# Loguino_v1_3.net
KiCad netlist of a schematic drawn in EAGLE
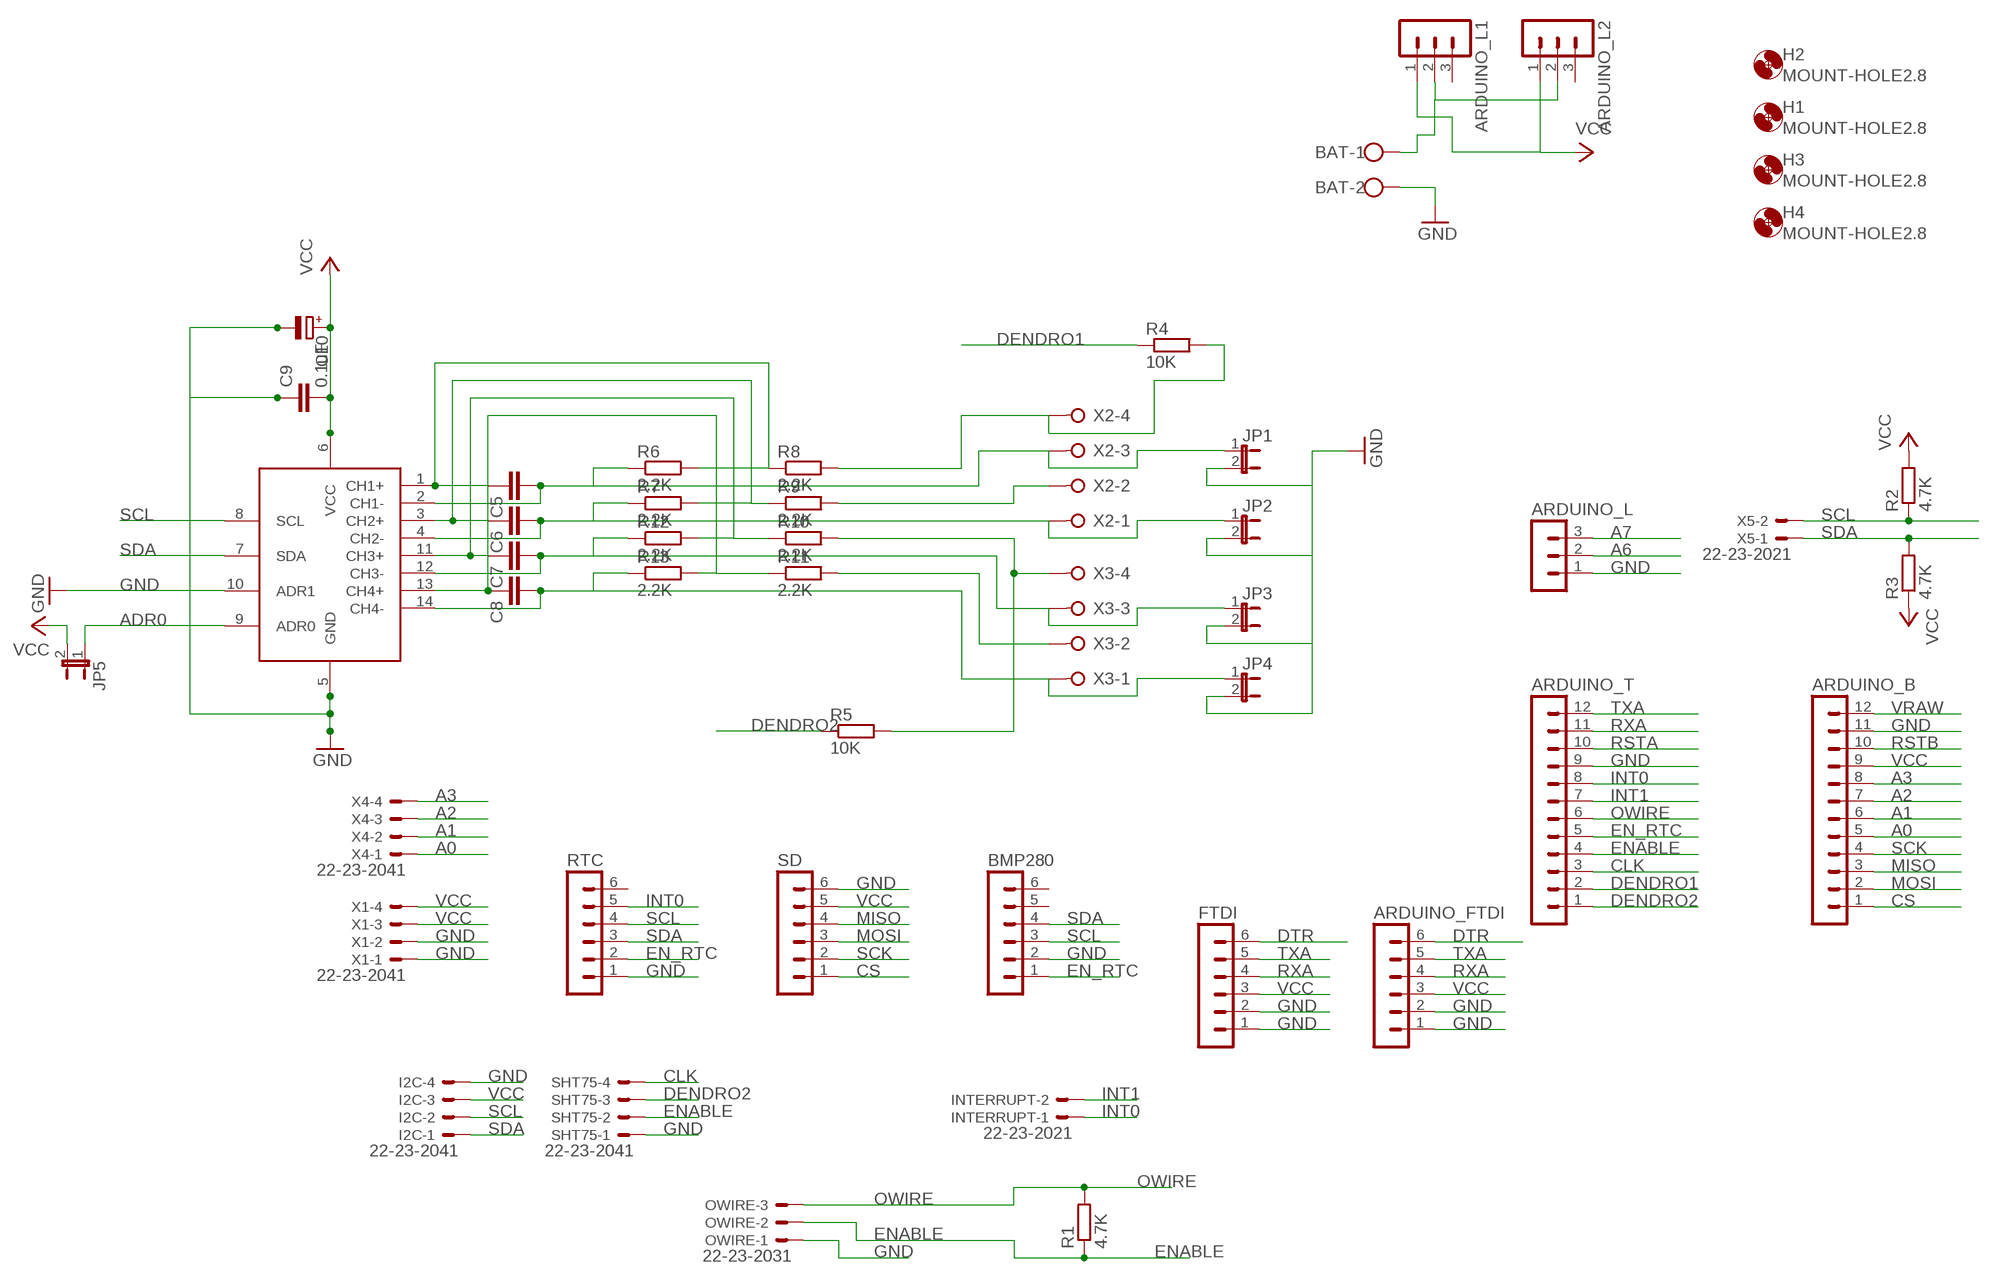
[diagram p0: schematic, sheet 1]

(export (version "E")
  (design (tool "Eeschema 10.0.6"))
  (components
    (comp (ref "ARDUINO_B")
      (value "MA12-1")
      (footprint "eagle-import:MA12-1")
      (libsource (lib "eagle-import") (part "MA12-1"))
    )
    (comp (ref "ARDUINO_FTDI")
      (value "MA06-1")
      (footprint "eagle-import:MA06-1")
      (libsource (lib "eagle-import") (part "MA06-1"))
    )
    (comp (ref "ARDUINO_L")
      (value "MA03-1")
      (footprint "eagle-import:MA03-1")
      (libsource (lib "eagle-import") (part "MA03-1"))
    )
    (comp (ref "ARDUINO_L1")
      (value "MA03-1")
      (footprint "eagle-import:MA03-1")
      (libsource (lib "eagle-import") (part "MA03-1"))
    )
    (comp (ref "ARDUINO_L2")
      (value "MA03-1")
      (footprint "eagle-import:MA03-1")
      (libsource (lib "eagle-import") (part "MA03-1"))
    )
    (comp (ref "ARDUINO_T")
      (value "MA12-1")
      (footprint "eagle-import:MA12-1")
      (libsource (lib "eagle-import") (part "MA12-1"))
    )
    (comp (ref "BAT")
      (value "W237-102")
      (footprint "eagle-import:W237-102")
      (fields (field (name "MPN") "237-102"))
      (libsource (lib "eagle-import") (part "W237-102"))
    )
    (comp (ref "BMP280")
      (value "MA06-1")
      (footprint "eagle-import:MA06-1")
      (libsource (lib "eagle-import") (part "MA06-1"))
    )
    (comp (ref "C5")
      (value "C-EU025-024X044")
      (footprint "eagle-import:C025-024X044")
      (libsource (lib "eagle-import") (part "C-EU025-024X044"))
    )
    (comp (ref "C6")
      (value "C-EU025-024X044")
      (footprint "eagle-import:C025-024X044")
      (libsource (lib "eagle-import") (part "C-EU025-024X044"))
    )
    (comp (ref "C7")
      (value "C-EU025-024X044")
      (footprint "eagle-import:C025-024X044")
      (libsource (lib "eagle-import") (part "C-EU025-024X044"))
    )
    (comp (ref "C8")
      (value "C-EU025-024X044")
      (footprint "eagle-import:C025-024X044")
      (libsource (lib "eagle-import") (part "C-EU025-024X044"))
    )
    (comp (ref "C9")
      (value "0.1uF")
      (footprint "eagle-import:C050-025X075")
      (libsource (lib "eagle-import") (part "C-EU050-025X075"))
    )
    (comp (ref "C10")
      (value "CPOL-EUE2,5-6E")
      (footprint "eagle-import:E2,5-6E")
      (libsource (lib "eagle-import") (part "CPOL-EUE2,5-6E"))
    )
    (comp (ref "FTDI")
      (value "MA06-1")
      (footprint "eagle-import:MA06-1")
      (libsource (lib "eagle-import") (part "MA06-1"))
    )
    (comp (ref "H1")
      (value "MOUNT-HOLE2.8")
      (footprint "eagle-import:2,8")
      (libsource (lib "eagle-import") (part "MOUNT-HOLE2.8"))
    )
    (comp (ref "H2")
      (value "MOUNT-HOLE2.8")
      (footprint "eagle-import:2,8")
      (libsource (lib "eagle-import") (part "MOUNT-HOLE2.8"))
    )
    (comp (ref "H3")
      (value "MOUNT-HOLE2.8")
      (footprint "eagle-import:2,8")
      (libsource (lib "eagle-import") (part "MOUNT-HOLE2.8"))
    )
    (comp (ref "H4")
      (value "MOUNT-HOLE2.8")
      (footprint "eagle-import:2,8")
      (libsource (lib "eagle-import") (part "MOUNT-HOLE2.8"))
    )
    (comp (ref "I2C")
      (value "22-23-2041")
      (footprint "eagle-import:22-23-2041")
      (fields (field (name "MF") "MOLEX"))
      (libsource (lib "eagle-import") (part "22-23-2041"))
    )
    (comp (ref "INTERRUPT")
      (value "22-23-2021")
      (footprint "eagle-import:22-23-2021")
      (fields (field (name "MF") "MOLEX"))
      (libsource (lib "eagle-import") (part "22-23-2021"))
    )
    (comp (ref "JP1")
      (value "JP1E")
      (footprint "eagle-import:JP1")
      (libsource (lib "eagle-import") (part "JP1E"))
    )
    (comp (ref "JP2")
      (value "JP1E")
      (footprint "eagle-import:JP1")
      (libsource (lib "eagle-import") (part "JP1E"))
    )
    (comp (ref "JP3")
      (value "JP1E")
      (footprint "eagle-import:JP1")
      (libsource (lib "eagle-import") (part "JP1E"))
    )
    (comp (ref "JP4")
      (value "JP1E")
      (footprint "eagle-import:JP1")
      (libsource (lib "eagle-import") (part "JP1E"))
    )
    (comp (ref "JP5")
      (value "JP1E")
      (footprint "eagle-import:JP1")
      (libsource (lib "eagle-import") (part "JP1E"))
    )
    (comp (ref "OWIRE")
      (value "22-23-2031")
      (footprint "eagle-import:22-23-2031")
      (fields (field (name "MF") "MOLEX"))
      (libsource (lib "eagle-import") (part "22-23-2031"))
    )
    (comp (ref "R1")
      (value "4.7K")
      (footprint "eagle-import:0204_7")
      (libsource (lib "eagle-import") (part "R-EU_0204/7"))
    )
    (comp (ref "R2")
      (value "4.7K")
      (footprint "eagle-import:0204_7")
      (libsource (lib "eagle-import") (part "R-EU_0204/7"))
    )
    (comp (ref "R3")
      (value "4.7K")
      (footprint "eagle-import:0204_7")
      (libsource (lib "eagle-import") (part "R-EU_0204/7"))
    )
    (comp (ref "R4")
      (value "10K")
      (footprint "eagle-import:0207_10")
      (libsource (lib "eagle-import") (part "resistor_R-EU_0207/10"))
    )
    (comp (ref "R5")
      (value "10K")
      (footprint "eagle-import:0207_10")
      (libsource (lib "eagle-import") (part "resistor_R-EU_0207/10"))
    )
    (comp (ref "R6")
      (value "2.2K")
      (footprint "eagle-import:0207_10")
      (libsource (lib "eagle-import") (part "resistor_R-EU_0207/10"))
    )
    (comp (ref "R7")
      (value "2.2K")
      (footprint "eagle-import:0207_10")
      (libsource (lib "eagle-import") (part "resistor_R-EU_0207/10"))
    )
    (comp (ref "R8")
      (value "2.2K")
      (footprint "eagle-import:0207_10")
      (libsource (lib "eagle-import") (part "resistor_R-EU_0207/10"))
    )
    (comp (ref "R9")
      (value "2.2K")
      (footprint "eagle-import:0207_10")
      (libsource (lib "eagle-import") (part "resistor_R-EU_0207/10"))
    )
    (comp (ref "R10")
      (value "2.2K")
      (footprint "eagle-import:0207_10")
      (libsource (lib "eagle-import") (part "resistor_R-EU_0207/10"))
    )
    (comp (ref "R11")
      (value "2.2K")
      (footprint "eagle-import:0207_10")
      (libsource (lib "eagle-import") (part "resistor_R-EU_0207/10"))
    )
    (comp (ref "R12")
      (value "2.2K")
      (footprint "eagle-import:0207_10")
      (libsource (lib "eagle-import") (part "resistor_R-EU_0207/10"))
    )
    (comp (ref "R13")
      (value "2.2K")
      (footprint "eagle-import:0207_10")
      (libsource (lib "eagle-import") (part "resistor_R-EU_0207/10"))
    )
    (comp (ref "RTC")
      (value "MA06-1")
      (footprint "eagle-import:MA06-1")
      (libsource (lib "eagle-import") (part "MA06-1"))
    )
    (comp (ref "SD")
      (value "MA06-1")
      (footprint "eagle-import:MA06-1")
      (libsource (lib "eagle-import") (part "MA06-1"))
    )
    (comp (ref "SHT75")
      (value "22-23-2041")
      (footprint "eagle-import:22-23-2041")
      (fields (field (name "MF") "MOLEX"))
      (libsource (lib "eagle-import") (part "22-23-2041"))
    )
    (comp (ref "U$2")
      (value "MCP342")
      (footprint "eagle-import:SO14")
      (libsource (lib "eagle-import") (part "MCP342"))
    )
    (comp (ref "X1")
      (value "22-23-2041")
      (footprint "eagle-import:22-23-2041")
      (fields (field (name "MF") "MOLEX"))
      (libsource (lib "eagle-import") (part "22-23-2041"))
    )
    (comp (ref "X2")
      (value "W237-04P")
      (footprint "eagle-import:W237-4P")
      (libsource (lib "eagle-import") (part "W237-04P"))
    )
    (comp (ref "X3")
      (value "W237-04P")
      (footprint "eagle-import:W237-4P")
      (libsource (lib "eagle-import") (part "W237-04P"))
    )
    (comp (ref "X4")
      (value "22-23-2041")
      (footprint "eagle-import:22-23-2041")
      (fields (field (name "MF") "MOLEX"))
      (libsource (lib "eagle-import") (part "22-23-2041"))
    )
    (comp (ref "X5")
      (value "22-23-2021")
      (footprint "eagle-import:22-23-2021")
      (fields (field (name "MF") "MOLEX"))
      (libsource (lib "eagle-import") (part "22-23-2021"))
    )
  )
  (nets
    (net (code "1") (name "/A0") (class "Default")
      (node (ref "ARDUINO_B") (pin "5") (pinfunction "5_5") (pintype "passive"))
      (node (ref "X4") (pin "1") (pinfunction "S_1") (pintype "passive"))
    )
    (net (code "2") (name "/A1") (class "Default")
      (node (ref "ARDUINO_B") (pin "6") (pinfunction "6_6") (pintype "passive"))
      (node (ref "X4") (pin "2") (pinfunction "S_2") (pintype "passive"))
    )
    (net (code "3") (name "/A2") (class "Default")
      (node (ref "ARDUINO_B") (pin "7") (pinfunction "7_7") (pintype "passive"))
      (node (ref "X4") (pin "3") (pinfunction "S_3") (pintype "passive"))
    )
    (net (code "4") (name "/A3") (class "Default")
      (node (ref "ARDUINO_B") (pin "8") (pinfunction "8_8") (pintype "passive"))
      (node (ref "X4") (pin "4") (pinfunction "S_4") (pintype "passive"))
    )
    (net (code "5") (name "/A6") (class "Default")
      (node (ref "ARDUINO_L") (pin "2") (pinfunction "2_2") (pintype "passive"))
    )
    (net (code "6") (name "/A7") (class "Default")
      (node (ref "ARDUINO_L") (pin "3") (pinfunction "3_3") (pintype "passive"))
    )
    (net (code "7") (name "/ADR0") (class "Default")
      (node (ref "JP5") (pin "1") (pinfunction "1_1") (pintype "passive"))
      (node (ref "U$2") (pin "9") (pinfunction "ADR0_9") (pintype "bidirectional"))
    )
    (net (code "8") (name "/CLK") (class "Default")
      (node (ref "ARDUINO_T") (pin "3") (pinfunction "3_3") (pintype "passive"))
      (node (ref "SHT75") (pin "4") (pinfunction "S_4") (pintype "passive"))
    )
    (net (code "9") (name "/CS") (class "Default")
      (node (ref "ARDUINO_B") (pin "1") (pinfunction "1_1") (pintype "passive"))
      (node (ref "SD") (pin "1") (pinfunction "1_1") (pintype "passive"))
    )
    (net (code "10") (name "/DENDRO1") (class "Default")
      (node (ref "ARDUINO_T") (pin "2") (pinfunction "2_2") (pintype "passive"))
      (node (ref "R4") (pin "1") (pinfunction "1_1") (pintype "passive"))
    )
    (net (code "11") (name "/DENDRO2") (class "Default")
      (node (ref "ARDUINO_T") (pin "1") (pinfunction "1_1") (pintype "passive"))
      (node (ref "R5") (pin "1") (pinfunction "1_1") (pintype "passive"))
      (node (ref "SHT75") (pin "3") (pinfunction "S_3") (pintype "passive"))
    )
    (net (code "12") (name "/DTR") (class "Default")
      (node (ref "ARDUINO_FTDI") (pin "6") (pinfunction "6_6") (pintype "passive"))
      (node (ref "FTDI") (pin "6") (pinfunction "6_6") (pintype "passive"))
    )
    (net (code "13") (name "/ENABLE") (class "Default")
      (node (ref "ARDUINO_T") (pin "4") (pinfunction "4_4") (pintype "passive"))
      (node (ref "OWIRE") (pin "2") (pinfunction "S_2") (pintype "passive"))
      (node (ref "R1") (pin "1") (pinfunction "1_1") (pintype "passive"))
      (node (ref "SHT75") (pin "2") (pinfunction "S_2") (pintype "passive"))
    )
    (net (code "14") (name "/EN_RTC") (class "Default")
      (node (ref "ARDUINO_T") (pin "5") (pinfunction "5_5") (pintype "passive"))
      (node (ref "BMP280") (pin "1") (pinfunction "1_1") (pintype "passive"))
      (node (ref "RTC") (pin "2") (pinfunction "2_2") (pintype "passive"))
    )
    (net (code "15") (name "/INT0") (class "Default")
      (node (ref "ARDUINO_T") (pin "8") (pinfunction "8_8") (pintype "passive"))
      (node (ref "INTERRUPT") (pin "1") (pinfunction "S_1") (pintype "passive"))
      (node (ref "RTC") (pin "5") (pinfunction "5_5") (pintype "passive"))
    )
    (net (code "16") (name "/INT1") (class "Default")
      (node (ref "ARDUINO_T") (pin "7") (pinfunction "7_7") (pintype "passive"))
      (node (ref "INTERRUPT") (pin "2") (pinfunction "S_2") (pintype "passive"))
    )
    (net (code "17") (name "/MISO") (class "Default")
      (node (ref "ARDUINO_B") (pin "3") (pinfunction "3_3") (pintype "passive"))
      (node (ref "SD") (pin "4") (pinfunction "4_4") (pintype "passive"))
    )
    (net (code "18") (name "/MOSI") (class "Default")
      (node (ref "ARDUINO_B") (pin "2") (pinfunction "2_2") (pintype "passive"))
      (node (ref "SD") (pin "3") (pinfunction "3_3") (pintype "passive"))
    )
    (net (code "19") (name "/OWIRE") (class "Default")
      (node (ref "ARDUINO_T") (pin "6") (pinfunction "6_6") (pintype "passive"))
      (node (ref "OWIRE") (pin "3") (pinfunction "S_3") (pintype "passive"))
      (node (ref "R1") (pin "2") (pinfunction "2_2") (pintype "passive"))
    )
    (net (code "20") (name "/RSTA") (class "Default")
      (node (ref "ARDUINO_T") (pin "10") (pinfunction "10_10") (pintype "passive"))
    )
    (net (code "21") (name "/RSTB") (class "Default")
      (node (ref "ARDUINO_B") (pin "10") (pinfunction "10_10") (pintype "passive"))
    )
    (net (code "22") (name "/RXA") (class "Default")
      (node (ref "ARDUINO_FTDI") (pin "4") (pinfunction "4_4") (pintype "passive"))
      (node (ref "ARDUINO_T") (pin "11") (pinfunction "11_11") (pintype "passive"))
      (node (ref "FTDI") (pin "4") (pinfunction "4_4") (pintype "passive"))
    )
    (net (code "23") (name "/SCK") (class "Default")
      (node (ref "ARDUINO_B") (pin "4") (pinfunction "4_4") (pintype "passive"))
      (node (ref "SD") (pin "2") (pinfunction "2_2") (pintype "passive"))
    )
    (net (code "24") (name "/SCL") (class "Default")
      (node (ref "BMP280") (pin "3") (pinfunction "3_3") (pintype "passive"))
      (node (ref "I2C") (pin "2") (pinfunction "S_2") (pintype "passive"))
      (node (ref "R2") (pin "1") (pinfunction "1_1") (pintype "passive"))
      (node (ref "RTC") (pin "4") (pinfunction "4_4") (pintype "passive"))
      (node (ref "U$2") (pin "8") (pinfunction "SCL_8") (pintype "bidirectional"))
      (node (ref "X5") (pin "2") (pinfunction "S_2") (pintype "passive"))
    )
    (net (code "25") (name "/SDA") (class "Default")
      (node (ref "BMP280") (pin "4") (pinfunction "4_4") (pintype "passive"))
      (node (ref "I2C") (pin "1") (pinfunction "S_1") (pintype "passive"))
      (node (ref "R3") (pin "2") (pinfunction "2_2") (pintype "passive"))
      (node (ref "RTC") (pin "3") (pinfunction "3_3") (pintype "passive"))
      (node (ref "U$2") (pin "7") (pinfunction "SDA_7") (pintype "bidirectional"))
      (node (ref "X5") (pin "1") (pinfunction "S_1") (pintype "passive"))
    )
    (net (code "26") (name "/TXA") (class "Default")
      (node (ref "ARDUINO_FTDI") (pin "5") (pinfunction "5_5") (pintype "passive"))
      (node (ref "ARDUINO_T") (pin "12") (pinfunction "12_12") (pintype "passive"))
      (node (ref "FTDI") (pin "5") (pinfunction "5_5") (pintype "passive"))
    )
    (net (code "27") (name "/VRAW") (class "Default")
      (node (ref "ARDUINO_B") (pin "12") (pinfunction "12_12") (pintype "passive"))
    )
    (net (code "28") (name "GND") (class "Default")
      (node (ref "ARDUINO_B") (pin "11") (pinfunction "11_11") (pintype "passive"))
      (node (ref "ARDUINO_FTDI") (pin "1") (pinfunction "1_1") (pintype "passive"))
      (node (ref "ARDUINO_FTDI") (pin "2") (pinfunction "2_2") (pintype "passive"))
      (node (ref "ARDUINO_L") (pin "1") (pinfunction "1_1") (pintype "passive"))
      (node (ref "ARDUINO_T") (pin "9") (pinfunction "9_9") (pintype "passive"))
      (node (ref "BAT") (pin "2") (pinfunction "KL_2") (pintype "passive"))
      (node (ref "BMP280") (pin "2") (pinfunction "2_2") (pintype "passive"))
      (node (ref "C10") (pin "-") (pinfunction "-_-") (pintype "passive"))
      (node (ref "C9") (pin "1") (pinfunction "1_1") (pintype "passive"))
      (node (ref "FTDI") (pin "1") (pinfunction "1_1") (pintype "passive"))
      (node (ref "FTDI") (pin "2") (pinfunction "2_2") (pintype "passive"))
      (node (ref "I2C") (pin "4") (pinfunction "S_4") (pintype "passive"))
      (node (ref "JP1") (pin "2") (pinfunction "2_2") (pintype "passive"))
      (node (ref "JP2") (pin "2") (pinfunction "2_2") (pintype "passive"))
      (node (ref "JP3") (pin "2") (pinfunction "2_2") (pintype "passive"))
      (node (ref "JP4") (pin "2") (pinfunction "2_2") (pintype "passive"))
      (node (ref "OWIRE") (pin "1") (pinfunction "S_1") (pintype "passive"))
      (node (ref "RTC") (pin "1") (pinfunction "1_1") (pintype "passive"))
      (node (ref "SD") (pin "6") (pinfunction "6_6") (pintype "passive"))
      (node (ref "SHT75") (pin "1") (pinfunction "S_1") (pintype "passive"))
      (node (ref "U$2") (pin "10") (pinfunction "ADR1_10") (pintype "bidirectional"))
      (node (ref "U$2") (pin "5") (pinfunction "GND_5") (pintype "bidirectional"))
      (node (ref "X1") (pin "1") (pinfunction "S_1") (pintype "passive"))
      (node (ref "X1") (pin "2") (pinfunction "S_2") (pintype "passive"))
    )
    (net (code "29") (name "Net-(BATA-KL)") (class "Default")
      (node (ref "ARDUINO_L1") (pin "2") (pinfunction "2_2") (pintype "passive"))
      (node (ref "ARDUINO_L2") (pin "2") (pinfunction "2_2") (pintype "passive"))
      (node (ref "BAT") (pin "1") (pinfunction "KL_1") (pintype "passive"))
    )
    (net (code "30") (name "Net-(U$2-CH1+)") (class "Default")
      (node (ref "C5") (pin "1") (pinfunction "1_1") (pintype "passive"))
      (node (ref "R6") (pin "2") (pinfunction "2_2") (pintype "passive"))
      (node (ref "R8") (pin "1") (pinfunction "1_1") (pintype "passive"))
      (node (ref "U$2") (pin "1") (pinfunction "CH1+_1") (pintype "bidirectional"))
    )
    (net (code "31") (name "Net-(U$2-CH1-)") (class "Default")
      (node (ref "C5") (pin "2") (pinfunction "2_2") (pintype "passive"))
      (node (ref "JP1") (pin "1") (pinfunction "1_1") (pintype "passive"))
      (node (ref "R6") (pin "1") (pinfunction "1_1") (pintype "passive"))
      (node (ref "U$2") (pin "2") (pinfunction "CH1-_2") (pintype "bidirectional"))
      (node (ref "X2") (pin "3") (pinfunction "KL_3") (pintype "passive"))
    )
    (net (code "32") (name "Net-(U$2-CH2+)") (class "Default")
      (node (ref "C6") (pin "1") (pinfunction "1_1") (pintype "passive"))
      (node (ref "R7") (pin "2") (pinfunction "2_2") (pintype "passive"))
      (node (ref "R9") (pin "1") (pinfunction "1_1") (pintype "passive"))
      (node (ref "U$2") (pin "3") (pinfunction "CH2+_3") (pintype "bidirectional"))
    )
    (net (code "33") (name "Net-(U$2-CH2-)") (class "Default")
      (node (ref "C6") (pin "2") (pinfunction "2_2") (pintype "passive"))
      (node (ref "JP2") (pin "1") (pinfunction "1_1") (pintype "passive"))
      (node (ref "R7") (pin "1") (pinfunction "1_1") (pintype "passive"))
      (node (ref "U$2") (pin "4") (pinfunction "CH2-_4") (pintype "bidirectional"))
      (node (ref "X2") (pin "1") (pinfunction "KL_1") (pintype "passive"))
    )
    (net (code "34") (name "Net-(U$2-CH3+)") (class "Default")
      (node (ref "C7") (pin "1") (pinfunction "1_1") (pintype "passive"))
      (node (ref "R10") (pin "1") (pinfunction "1_1") (pintype "passive"))
      (node (ref "R12") (pin "2") (pinfunction "2_2") (pintype "passive"))
      (node (ref "U$2") (pin "11") (pinfunction "CH3+_11") (pintype "bidirectional"))
    )
    (net (code "35") (name "Net-(U$2-CH3-)") (class "Default")
      (node (ref "C7") (pin "2") (pinfunction "2_2") (pintype "passive"))
      (node (ref "JP3") (pin "1") (pinfunction "1_1") (pintype "passive"))
      (node (ref "R12") (pin "1") (pinfunction "1_1") (pintype "passive"))
      (node (ref "U$2") (pin "12") (pinfunction "CH3-_12") (pintype "bidirectional"))
      (node (ref "X3") (pin "3") (pinfunction "KL_3") (pintype "passive"))
    )
    (net (code "36") (name "Net-(U$2-CH4+)") (class "Default")
      (node (ref "C8") (pin "1") (pinfunction "1_1") (pintype "passive"))
      (node (ref "R11") (pin "1") (pinfunction "1_1") (pintype "passive"))
      (node (ref "R13") (pin "2") (pinfunction "2_2") (pintype "passive"))
      (node (ref "U$2") (pin "13") (pinfunction "CH4+_13") (pintype "bidirectional"))
    )
    (net (code "37") (name "Net-(U$2-CH4-)") (class "Default")
      (node (ref "C8") (pin "2") (pinfunction "2_2") (pintype "passive"))
      (node (ref "JP4") (pin "1") (pinfunction "1_1") (pintype "passive"))
      (node (ref "R13") (pin "1") (pinfunction "1_1") (pintype "passive"))
      (node (ref "U$2") (pin "14") (pinfunction "CH4-_14") (pintype "bidirectional"))
      (node (ref "X3") (pin "1") (pinfunction "KL_1") (pintype "passive"))
    )
    (net (code "38") (name "Net-(X2B-KL)") (class "Default")
      (node (ref "R9") (pin "2") (pinfunction "2_2") (pintype "passive"))
      (node (ref "X2") (pin "2") (pinfunction "KL_2") (pintype "passive"))
    )
    (net (code "39") (name "Net-(X2D-KL)") (class "Default")
      (node (ref "R4") (pin "2") (pinfunction "2_2") (pintype "passive"))
      (node (ref "R8") (pin "2") (pinfunction "2_2") (pintype "passive"))
      (node (ref "X2") (pin "4") (pinfunction "KL_4") (pintype "passive"))
    )
    (net (code "40") (name "Net-(X3B-KL)") (class "Default")
      (node (ref "R11") (pin "2") (pinfunction "2_2") (pintype "passive"))
      (node (ref "X3") (pin "2") (pinfunction "KL_2") (pintype "passive"))
    )
    (net (code "41") (name "Net-(X3D-KL)") (class "Default")
      (node (ref "R10") (pin "2") (pinfunction "2_2") (pintype "passive"))
      (node (ref "R5") (pin "2") (pinfunction "2_2") (pintype "passive"))
      (node (ref "X3") (pin "4") (pinfunction "KL_4") (pintype "passive"))
    )
    (net (code "42") (name "VCC") (class "Default")
      (node (ref "ARDUINO_B") (pin "9") (pinfunction "9_9") (pintype "passive"))
      (node (ref "ARDUINO_FTDI") (pin "3") (pinfunction "3_3") (pintype "passive"))
      (node (ref "ARDUINO_L1") (pin "1") (pinfunction "1_1") (pintype "passive"))
      (node (ref "ARDUINO_L2") (pin "1") (pinfunction "1_1") (pintype "passive"))
      (node (ref "C10") (pin "+") (pinfunction "+_+") (pintype "passive"))
      (node (ref "C9") (pin "2") (pinfunction "2_2") (pintype "passive"))
      (node (ref "FTDI") (pin "3") (pinfunction "3_3") (pintype "passive"))
      (node (ref "I2C") (pin "3") (pinfunction "S_3") (pintype "passive"))
      (node (ref "JP5") (pin "2") (pinfunction "2_2") (pintype "passive"))
      (node (ref "R2") (pin "2") (pinfunction "2_2") (pintype "passive"))
      (node (ref "R3") (pin "1") (pinfunction "1_1") (pintype "passive"))
      (node (ref "SD") (pin "5") (pinfunction "5_5") (pintype "passive"))
      (node (ref "U$2") (pin "6") (pinfunction "VCC_6") (pintype "bidirectional"))
      (node (ref "X1") (pin "3") (pinfunction "S_3") (pintype "passive"))
      (node (ref "X1") (pin "4") (pinfunction "S_4") (pintype "passive"))
    )
    (net (code "43") (name "unconnected-(ARDUINO_L1-Pad3)") (class "Default")
      (node (ref "ARDUINO_L1") (pin "3") (pinfunction "3_3") (pintype "passive"))
    )
    (net (code "44") (name "unconnected-(ARDUINO_L2-Pad3)") (class "Default")
      (node (ref "ARDUINO_L2") (pin "3") (pinfunction "3_3") (pintype "passive"))
    )
    (net (code "45") (name "unconnected-(BMP280-Pad5)") (class "Default")
      (node (ref "BMP280") (pin "5") (pinfunction "5_5") (pintype "passive"))
    )
    (net (code "46") (name "unconnected-(BMP280-Pad6)") (class "Default")
      (node (ref "BMP280") (pin "6") (pinfunction "6_6") (pintype "passive"))
    )
    (net (code "47") (name "unconnected-(RTC-Pad6)") (class "Default")
      (node (ref "RTC") (pin "6") (pinfunction "6_6") (pintype "passive"))
    )
  )
)
